# Minimal.net
KiCad netlist of a schematic drawn in EAGLE
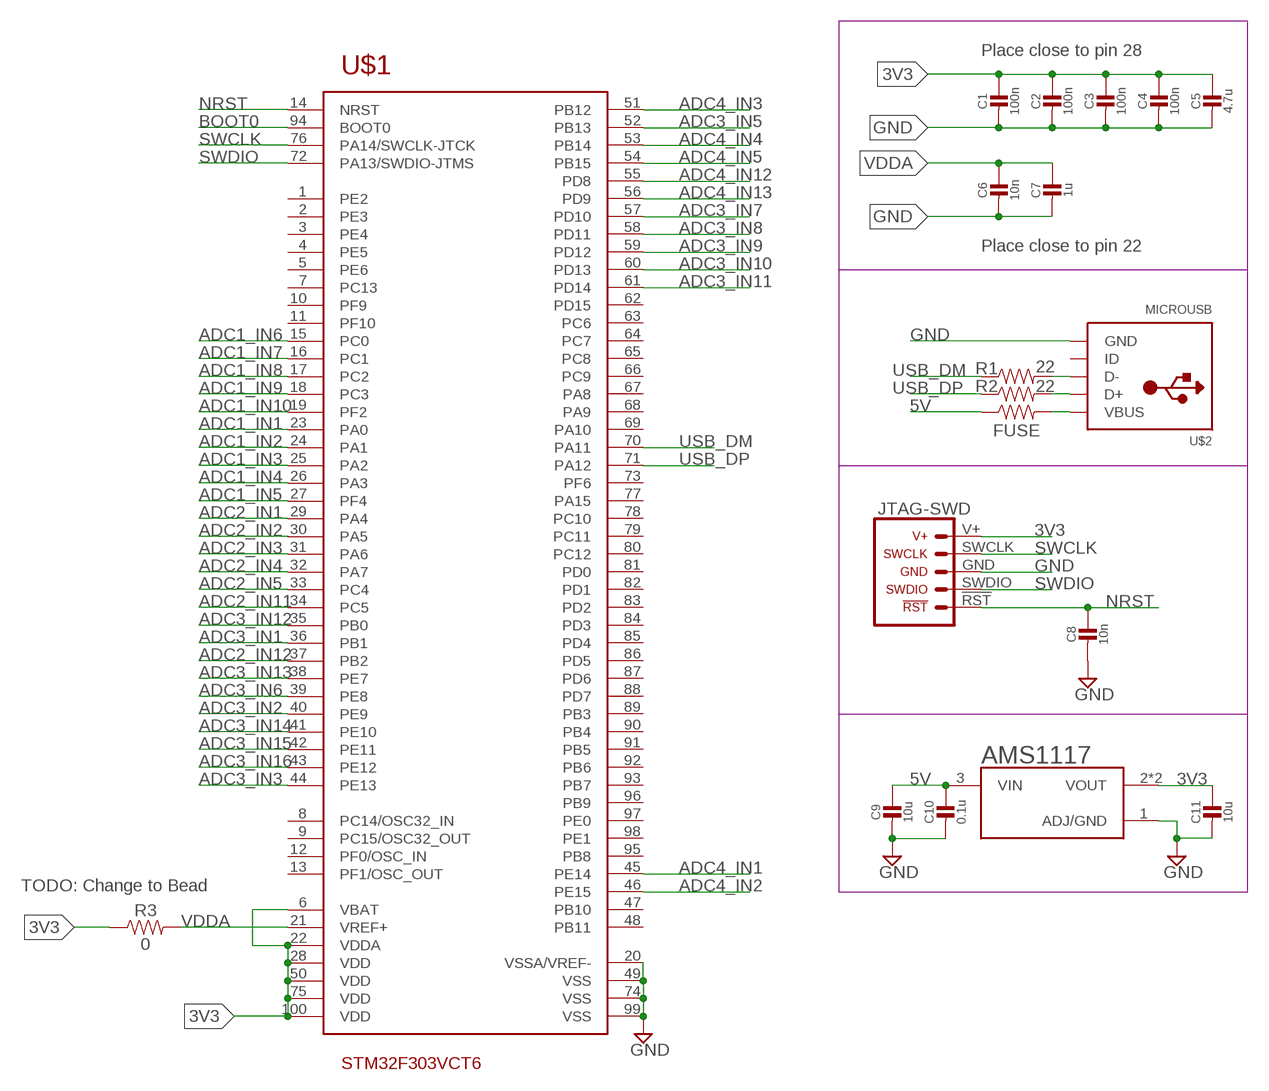
[diagram p0: schematic, sheet 1]
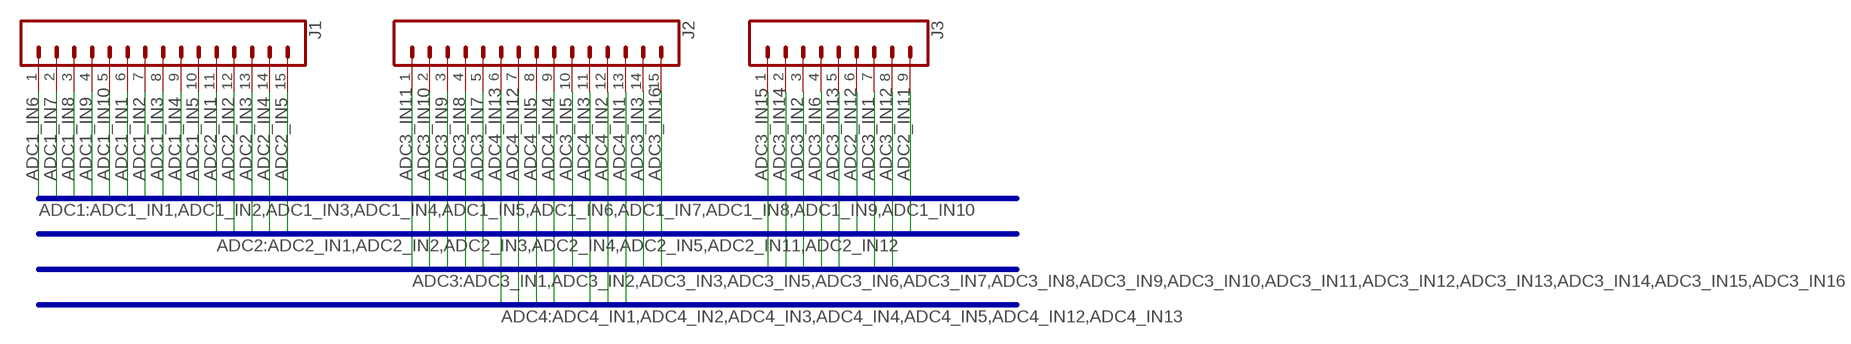
[diagram p1: schematic, sheet 2]

(export (version "E")
  (design (tool "Eeschema 10.0.6"))
  (components
    (comp (ref "J1")
      (value "CONN_15")
      (footprint "eagle-import:1X15")
      (libsource (lib "eagle-import") (part "CONN_15"))
    )
    (comp (ref "J2")
      (value "CONN_15")
      (footprint "eagle-import:1X15")
      (libsource (lib "eagle-import") (part "CONN_15"))
    )
    (comp (ref "J3")
      (value "CONN_09")
      (footprint "eagle-import:1X09")
      (libsource (lib "eagle-import") (part "CONN_09"))
    )
    (comp (ref "AMS1117")
      (value "3.3V")
      (footprint "eagle-import:SOT89")
      (libsource (lib "eagle-import") (part "VREG_AMS1117SMALL"))
    )
    (comp (ref "C1")
      (value "100n")
      (footprint "eagle-import:CAP_0603")
      (libsource (lib "eagle-import") (part "CAP_CERAMIC_0603"))
    )
    (comp (ref "C2")
      (value "100n")
      (footprint "eagle-import:CAP_0603")
      (libsource (lib "eagle-import") (part "CAP_CERAMIC_0603"))
    )
    (comp (ref "C3")
      (value "100n")
      (footprint "eagle-import:CAP_0603")
      (libsource (lib "eagle-import") (part "CAP_CERAMIC_0603"))
    )
    (comp (ref "C4")
      (value "100n")
      (footprint "eagle-import:CAP_0603")
      (libsource (lib "eagle-import") (part "CAP_CERAMIC_0603"))
    )
    (comp (ref "C5")
      (value "4.7u")
      (footprint "eagle-import:CAP_0603")
      (libsource (lib "eagle-import") (part "CAP_CERAMIC_0603"))
    )
    (comp (ref "C6")
      (value "10n")
      (footprint "eagle-import:CAP_0603")
      (libsource (lib "eagle-import") (part "CAP_CERAMIC_0603"))
    )
    (comp (ref "C7")
      (value "1u")
      (footprint "eagle-import:CAP_0603")
      (libsource (lib "eagle-import") (part "CAP_CERAMIC_0603"))
    )
    (comp (ref "C8")
      (value "10n")
      (footprint "eagle-import:CAP_0603")
      (libsource (lib "eagle-import") (part "CAP_CERAMIC_0603"))
    )
    (comp (ref "C9")
      (value "10u")
      (footprint "eagle-import:CAP_0603")
      (libsource (lib "eagle-import") (part "CAP_CERAMIC_0603"))
    )
    (comp (ref "C10")
      (value "0.1u")
      (footprint "eagle-import:CAP_0603")
      (libsource (lib "eagle-import") (part "CAP_CERAMIC_0603"))
    )
    (comp (ref "C11")
      (value "10u")
      (footprint "eagle-import:CAP_0603")
      (libsource (lib "eagle-import") (part "CAP_CERAMIC_0603"))
    )
    (comp (ref "FUSE")
      (value "RESISTOR1206")
      (footprint "eagle-import:1206")
      (libsource (lib "eagle-import") (part "RESISTOR1206"))
    )
    (comp (ref "R1")
      (value "22")
      (footprint "eagle-import:0603")
      (libsource (lib "eagle-import") (part "RESISTOR0603"))
    )
    (comp (ref "R2")
      (value "22")
      (footprint "eagle-import:0603")
      (libsource (lib "eagle-import") (part "RESISTOR0603"))
    )
    (comp (ref "R3")
      (value "0")
      (footprint "eagle-import:0603")
      (libsource (lib "eagle-import") (part "RESISTOR0603"))
    )
    (comp (ref "U$1")
      (value "STM32F303VCT6")
      (footprint "eagle-import:LQFP-100")
      (libsource (lib "eagle-import") (part "STM32F303VCT6"))
    )
    (comp (ref "U$2")
      (value "MICROUSB")
      (footprint "eagle-import:MICROUSB")
      (libsource (lib "eagle-import") (part "MICROUSB"))
    )
    (comp (ref "U$3")
      (value "JTAG-SWD")
      (footprint "eagle-import:JTAG_SWD")
      (libsource (lib "eagle-import") (part "JTAG-SWD"))
    )
  )
  (nets
    (net (code "9") (name "3V3") (class "Default")
      (node (ref "AMS1117") (pin "2") (pinfunction "VOUT_2") (pintype "output"))
      (node (ref "AMS1117") (pin "2@1") (pinfunction "VOUT_2@1") (pintype "output"))
      (node (ref "C1") (pin "1") (pinfunction "1_1") (pintype "passive"))
      (node (ref "C11") (pin "1") (pinfunction "1_1") (pintype "passive"))
      (node (ref "C2") (pin "1") (pinfunction "1_1") (pintype "passive"))
      (node (ref "C3") (pin "1") (pinfunction "1_1") (pintype "passive"))
      (node (ref "C4") (pin "1") (pinfunction "1_1") (pintype "passive"))
      (node (ref "C5") (pin "1") (pinfunction "1_1") (pintype "passive"))
      (node (ref "R3") (pin "1") (pinfunction "1_1") (pintype "passive"))
      (node (ref "U$1") (pin "100") (pinfunction "VDD_100") (pintype "bidirectional"))
      (node (ref "U$1") (pin "22") (pinfunction "VDDA_22") (pintype "bidirectional"))
      (node (ref "U$1") (pin "28") (pinfunction "VDD_28") (pintype "bidirectional"))
      (node (ref "U$1") (pin "50") (pinfunction "VDD_50") (pintype "bidirectional"))
      (node (ref "U$1") (pin "6") (pinfunction "VBAT_6") (pintype "bidirectional"))
      (node (ref "U$1") (pin "75") (pinfunction "VDD_75") (pintype "bidirectional"))
      (node (ref "U$3") (pin "V+") (pinfunction "V+_V+") (pintype "passive"))
    )
    (net (code "10") (name "5V") (class "Default")
      (node (ref "AMS1117") (pin "3") (pinfunction "VIN_3") (pintype "input"))
      (node (ref "C10") (pin "1") (pinfunction "1_1") (pintype "passive"))
      (node (ref "C9") (pin "1") (pinfunction "1_1") (pintype "passive"))
      (node (ref "FUSE") (pin "1") (pinfunction "1_1") (pintype "passive"))
    )
    (net (code "11") (name "ADC1_IN1") (class "Default")
      (node (ref "J1") (pin "6") (pinfunction "6_6") (pintype "passive"))
      (node (ref "U$1") (pin "23") (pinfunction "PA0_23") (pintype "bidirectional"))
    )
    (net (code "12") (name "ADC1_IN2") (class "Default")
      (node (ref "J1") (pin "7") (pinfunction "7_7") (pintype "passive"))
      (node (ref "U$1") (pin "24") (pinfunction "PA1_24") (pintype "bidirectional"))
    )
    (net (code "13") (name "ADC1_IN3") (class "Default")
      (node (ref "J1") (pin "8") (pinfunction "8_8") (pintype "passive"))
      (node (ref "U$1") (pin "25") (pinfunction "PA2_25") (pintype "bidirectional"))
    )
    (net (code "14") (name "ADC1_IN4") (class "Default")
      (node (ref "J1") (pin "9") (pinfunction "9_9") (pintype "passive"))
      (node (ref "U$1") (pin "26") (pinfunction "PA3_26") (pintype "bidirectional"))
    )
    (net (code "15") (name "ADC1_IN5") (class "Default")
      (node (ref "J1") (pin "10") (pinfunction "10_10") (pintype "passive"))
      (node (ref "U$1") (pin "27") (pinfunction "PF4_27") (pintype "bidirectional"))
    )
    (net (code "16") (name "ADC1_IN6") (class "Default")
      (node (ref "J1") (pin "1") (pinfunction "1_1") (pintype "passive"))
      (node (ref "U$1") (pin "15") (pinfunction "PC0_15") (pintype "bidirectional"))
    )
    (net (code "17") (name "ADC1_IN7") (class "Default")
      (node (ref "J1") (pin "2") (pinfunction "2_2") (pintype "passive"))
      (node (ref "U$1") (pin "16") (pinfunction "PC1_16") (pintype "bidirectional"))
    )
    (net (code "18") (name "ADC1_IN8") (class "Default")
      (node (ref "J1") (pin "3") (pinfunction "3_3") (pintype "passive"))
      (node (ref "U$1") (pin "17") (pinfunction "PC2_17") (pintype "bidirectional"))
    )
    (net (code "19") (name "ADC1_IN9") (class "Default")
      (node (ref "J1") (pin "4") (pinfunction "4_4") (pintype "passive"))
      (node (ref "U$1") (pin "18") (pinfunction "PC3_18") (pintype "bidirectional"))
    )
    (net (code "20") (name "ADC1_IN10") (class "Default")
      (node (ref "J1") (pin "5") (pinfunction "5_5") (pintype "passive"))
      (node (ref "U$1") (pin "19") (pinfunction "PF2_19") (pintype "bidirectional"))
    )
    (net (code "21") (name "ADC2_IN1") (class "Default")
      (node (ref "J1") (pin "11") (pinfunction "11_11") (pintype "passive"))
      (node (ref "U$1") (pin "29") (pinfunction "PA4_29") (pintype "bidirectional"))
    )
    (net (code "22") (name "ADC2_IN2") (class "Default")
      (node (ref "J1") (pin "12") (pinfunction "12_12") (pintype "passive"))
      (node (ref "U$1") (pin "30") (pinfunction "PA5_30") (pintype "bidirectional"))
    )
    (net (code "23") (name "ADC2_IN3") (class "Default")
      (node (ref "J1") (pin "13") (pinfunction "13_13") (pintype "passive"))
      (node (ref "U$1") (pin "31") (pinfunction "PA6_31") (pintype "bidirectional"))
    )
    (net (code "24") (name "ADC2_IN4") (class "Default")
      (node (ref "J1") (pin "14") (pinfunction "14_14") (pintype "passive"))
      (node (ref "U$1") (pin "32") (pinfunction "PA7_32") (pintype "bidirectional"))
    )
    (net (code "25") (name "ADC2_IN5") (class "Default")
      (node (ref "J1") (pin "15") (pinfunction "15_15") (pintype "passive"))
      (node (ref "U$1") (pin "33") (pinfunction "PC4_33") (pintype "bidirectional"))
    )
    (net (code "26") (name "ADC2_IN11") (class "Default")
      (node (ref "J3") (pin "9") (pinfunction "9_9") (pintype "passive"))
      (node (ref "U$1") (pin "34") (pinfunction "PC5_34") (pintype "bidirectional"))
    )
    (net (code "27") (name "ADC2_IN12") (class "Default")
      (node (ref "J3") (pin "6") (pinfunction "6_6") (pintype "passive"))
      (node (ref "U$1") (pin "37") (pinfunction "PB2_37") (pintype "bidirectional"))
    )
    (net (code "28") (name "ADC3_IN1") (class "Default")
      (node (ref "J3") (pin "7") (pinfunction "7_7") (pintype "passive"))
      (node (ref "U$1") (pin "36") (pinfunction "PB1_36") (pintype "bidirectional"))
    )
    (net (code "29") (name "ADC3_IN2") (class "Default")
      (node (ref "J3") (pin "3") (pinfunction "3_3") (pintype "passive"))
      (node (ref "U$1") (pin "40") (pinfunction "PE9_40") (pintype "bidirectional"))
    )
    (net (code "30") (name "ADC3_IN3") (class "Default")
      (node (ref "J2") (pin "14") (pinfunction "14_14") (pintype "passive"))
      (node (ref "U$1") (pin "44") (pinfunction "PE13_44") (pintype "bidirectional"))
    )
    (net (code "31") (name "ADC3_IN5") (class "Default")
      (node (ref "J2") (pin "10") (pinfunction "10_10") (pintype "passive"))
      (node (ref "U$1") (pin "52") (pinfunction "PB13_52") (pintype "bidirectional"))
    )
    (net (code "32") (name "ADC3_IN6") (class "Default")
      (node (ref "J3") (pin "4") (pinfunction "4_4") (pintype "passive"))
      (node (ref "U$1") (pin "39") (pinfunction "PE8_39") (pintype "bidirectional"))
    )
    (net (code "33") (name "ADC3_IN7") (class "Default")
      (node (ref "J2") (pin "5") (pinfunction "5_5") (pintype "passive"))
      (node (ref "U$1") (pin "57") (pinfunction "PD10_57") (pintype "bidirectional"))
    )
    (net (code "34") (name "ADC3_IN8") (class "Default")
      (node (ref "J2") (pin "4") (pinfunction "4_4") (pintype "passive"))
      (node (ref "U$1") (pin "58") (pinfunction "PD11_58") (pintype "bidirectional"))
    )
    (net (code "35") (name "ADC3_IN9") (class "Default")
      (node (ref "J2") (pin "3") (pinfunction "3_3") (pintype "passive"))
      (node (ref "U$1") (pin "59") (pinfunction "PD12_59") (pintype "bidirectional"))
    )
    (net (code "36") (name "ADC3_IN10") (class "Default")
      (node (ref "J2") (pin "2") (pinfunction "2_2") (pintype "passive"))
      (node (ref "U$1") (pin "60") (pinfunction "PD13_60") (pintype "bidirectional"))
    )
    (net (code "37") (name "ADC3_IN11") (class "Default")
      (node (ref "J2") (pin "1") (pinfunction "1_1") (pintype "passive"))
      (node (ref "U$1") (pin "61") (pinfunction "PD14_61") (pintype "bidirectional"))
    )
    (net (code "38") (name "ADC3_IN12") (class "Default")
      (node (ref "J3") (pin "8") (pinfunction "8_8") (pintype "passive"))
      (node (ref "U$1") (pin "35") (pinfunction "PB0_35") (pintype "bidirectional"))
    )
    (net (code "39") (name "ADC3_IN13") (class "Default")
      (node (ref "J3") (pin "5") (pinfunction "5_5") (pintype "passive"))
      (node (ref "U$1") (pin "38") (pinfunction "PE7_38") (pintype "bidirectional"))
    )
    (net (code "40") (name "ADC3_IN14") (class "Default")
      (node (ref "J3") (pin "2") (pinfunction "2_2") (pintype "passive"))
      (node (ref "U$1") (pin "41") (pinfunction "PE10_41") (pintype "bidirectional"))
    )
    (net (code "41") (name "ADC3_IN15") (class "Default")
      (node (ref "J3") (pin "1") (pinfunction "1_1") (pintype "passive"))
      (node (ref "U$1") (pin "42") (pinfunction "PE11_42") (pintype "bidirectional"))
    )
    (net (code "42") (name "ADC3_IN16") (class "Default")
      (node (ref "J2") (pin "15") (pinfunction "15_15") (pintype "passive"))
      (node (ref "U$1") (pin "43") (pinfunction "PE12_43") (pintype "bidirectional"))
    )
    (net (code "43") (name "ADC4_IN1") (class "Default")
      (node (ref "J2") (pin "13") (pinfunction "13_13") (pintype "passive"))
      (node (ref "U$1") (pin "45") (pinfunction "PE14_45") (pintype "bidirectional"))
    )
    (net (code "44") (name "ADC4_IN2") (class "Default")
      (node (ref "J2") (pin "12") (pinfunction "12_12") (pintype "passive"))
      (node (ref "U$1") (pin "46") (pinfunction "PE15_46") (pintype "bidirectional"))
    )
    (net (code "45") (name "ADC4_IN3") (class "Default")
      (node (ref "J2") (pin "11") (pinfunction "11_11") (pintype "passive"))
      (node (ref "U$1") (pin "51") (pinfunction "PB12_51") (pintype "bidirectional"))
    )
    (net (code "46") (name "ADC4_IN4") (class "Default")
      (node (ref "J2") (pin "9") (pinfunction "9_9") (pintype "passive"))
      (node (ref "U$1") (pin "53") (pinfunction "PB14_53") (pintype "bidirectional"))
    )
    (net (code "47") (name "ADC4_IN5") (class "Default")
      (node (ref "J2") (pin "8") (pinfunction "8_8") (pintype "passive"))
      (node (ref "U$1") (pin "54") (pinfunction "PB15_54") (pintype "bidirectional"))
    )
    (net (code "48") (name "ADC4_IN12") (class "Default")
      (node (ref "J2") (pin "7") (pinfunction "7_7") (pintype "passive"))
      (node (ref "U$1") (pin "55") (pinfunction "PD8_55") (pintype "bidirectional"))
    )
    (net (code "49") (name "ADC4_IN13") (class "Default")
      (node (ref "J2") (pin "6") (pinfunction "6_6") (pintype "passive"))
      (node (ref "U$1") (pin "56") (pinfunction "PD9_56") (pintype "bidirectional"))
    )
    (net (code "50") (name "BOOT0") (class "Default")
      (node (ref "U$1") (pin "94") (pinfunction "BOOT0_94") (pintype "bidirectional"))
    )
    (net (code "51") (name "GND") (class "Default")
      (node (ref "AMS1117") (pin "1") (pinfunction "ADJ/GND_1") (pintype "power_in"))
      (node (ref "C1") (pin "2") (pinfunction "2_2") (pintype "passive"))
      (node (ref "C10") (pin "2") (pinfunction "2_2") (pintype "passive"))
      (node (ref "C11") (pin "2") (pinfunction "2_2") (pintype "passive"))
      (node (ref "C2") (pin "2") (pinfunction "2_2") (pintype "passive"))
      (node (ref "C3") (pin "2") (pinfunction "2_2") (pintype "passive"))
      (node (ref "C4") (pin "2") (pinfunction "2_2") (pintype "passive"))
      (node (ref "C5") (pin "2") (pinfunction "2_2") (pintype "passive"))
      (node (ref "C6") (pin "2") (pinfunction "2_2") (pintype "passive"))
      (node (ref "C7") (pin "2") (pinfunction "2_2") (pintype "passive"))
      (node (ref "C8") (pin "2") (pinfunction "2_2") (pintype "passive"))
      (node (ref "C9") (pin "2") (pinfunction "2_2") (pintype "passive"))
      (node (ref "U$1") (pin "20") (pinfunction "VSSA/VREF-_20") (pintype "bidirectional"))
      (node (ref "U$1") (pin "49") (pinfunction "VSS_49") (pintype "bidirectional"))
      (node (ref "U$1") (pin "74") (pinfunction "VSS_74") (pintype "bidirectional"))
      (node (ref "U$1") (pin "99") (pinfunction "VSS_99") (pintype "bidirectional"))
      (node (ref "U$2") (pin "GND") (pinfunction "GND_GND") (pintype "power_in"))
      (node (ref "U$2") (pin "S1") (pinfunction "GND_S1") (pintype "power_in"))
      (node (ref "U$2") (pin "S2") (pinfunction "GND_S2") (pintype "power_in"))
      (node (ref "U$2") (pin "S3") (pinfunction "GND_S3") (pintype "power_in"))
      (node (ref "U$2") (pin "S4") (pinfunction "GND_S4") (pintype "power_in"))
      (node (ref "U$2") (pin "S5") (pinfunction "GND_S5") (pintype "power_in"))
      (node (ref "U$2") (pin "S6") (pinfunction "GND_S6") (pintype "power_in"))
      (node (ref "U$3") (pin "GND") (pinfunction "GND_GND") (pintype "passive"))
    )
    (net (code "52") (name "NRST") (class "Default")
      (node (ref "C8") (pin "1") (pinfunction "1_1") (pintype "passive"))
      (node (ref "U$1") (pin "14") (pinfunction "NRST_14") (pintype "bidirectional"))
      (node (ref "U$3") (pin "!RST") (pinfunction "~{RST}_!RST") (pintype "passive"))
    )
    (net (code "53") (name "Net-(FUSE-Pad2)") (class "Default")
      (node (ref "FUSE") (pin "2") (pinfunction "2_2") (pintype "passive"))
      (node (ref "U$2") (pin "VBUS") (pinfunction "VBUS_VBUS") (pintype "power_in"))
    )
    (net (code "54") (name "Net-(R1-Pad2)") (class "Default")
      (node (ref "R1") (pin "2") (pinfunction "2_2") (pintype "passive"))
      (node (ref "U$2") (pin "D-") (pinfunction "D-_D-") (pintype "bidirectional"))
    )
    (net (code "55") (name "Net-(R2-Pad2)") (class "Default")
      (node (ref "R2") (pin "2") (pinfunction "2_2") (pintype "passive"))
      (node (ref "U$2") (pin "D+") (pinfunction "D+_D+") (pintype "bidirectional"))
    )
    (net (code "56") (name "SWCLK") (class "Default")
      (node (ref "U$1") (pin "76") (pinfunction "PA14/SWCLK-JTCK_76") (pintype "bidirectional"))
      (node (ref "U$3") (pin "SWCLK") (pinfunction "SWCLK_SWCLK") (pintype "passive"))
    )
    (net (code "57") (name "SWDIO") (class "Default")
      (node (ref "U$1") (pin "72") (pinfunction "PA13/SWDIO-JTMS_72") (pintype "bidirectional"))
      (node (ref "U$3") (pin "SWDIO") (pinfunction "SWDIO_SWDIO") (pintype "passive"))
    )
    (net (code "58") (name "USB_DM") (class "Default")
      (node (ref "R1") (pin "1") (pinfunction "1_1") (pintype "passive"))
      (node (ref "U$1") (pin "70") (pinfunction "PA11_70") (pintype "bidirectional"))
    )
    (net (code "59") (name "USB_DP") (class "Default")
      (node (ref "R2") (pin "1") (pinfunction "1_1") (pintype "passive"))
      (node (ref "U$1") (pin "71") (pinfunction "PA12_71") (pintype "bidirectional"))
    )
    (net (code "60") (name "VDDA") (class "Default")
      (node (ref "C6") (pin "1") (pinfunction "1_1") (pintype "passive"))
      (node (ref "C7") (pin "1") (pinfunction "1_1") (pintype "passive"))
      (node (ref "R3") (pin "2") (pinfunction "2_2") (pintype "passive"))
      (node (ref "U$1") (pin "21") (pinfunction "VREF+_21") (pintype "bidirectional"))
    )
    (net (code "61") (name "unconnected-(U$1-PA8-Pad67)") (class "Default")
      (node (ref "U$1") (pin "67") (pinfunction "PA8_67") (pintype "bidirectional"))
    )
    (net (code "62") (name "unconnected-(U$1-PA9-Pad68)") (class "Default")
      (node (ref "U$1") (pin "68") (pinfunction "PA9_68") (pintype "bidirectional"))
    )
    (net (code "63") (name "unconnected-(U$1-PA10-Pad69)") (class "Default")
      (node (ref "U$1") (pin "69") (pinfunction "PA10_69") (pintype "bidirectional"))
    )
    (net (code "64") (name "unconnected-(U$1-PA15-Pad77)") (class "Default")
      (node (ref "U$1") (pin "77") (pinfunction "PA15_77") (pintype "bidirectional"))
    )
    (net (code "65") (name "unconnected-(U$1-PB3-Pad89)") (class "Default")
      (node (ref "U$1") (pin "89") (pinfunction "PB3_89") (pintype "bidirectional"))
    )
    (net (code "66") (name "unconnected-(U$1-PB4-Pad90)") (class "Default")
      (node (ref "U$1") (pin "90") (pinfunction "PB4_90") (pintype "bidirectional"))
    )
    (net (code "67") (name "unconnected-(U$1-PB5-Pad91)") (class "Default")
      (node (ref "U$1") (pin "91") (pinfunction "PB5_91") (pintype "bidirectional"))
    )
    (net (code "68") (name "unconnected-(U$1-PB6-Pad92)") (class "Default")
      (node (ref "U$1") (pin "92") (pinfunction "PB6_92") (pintype "bidirectional"))
    )
    (net (code "69") (name "unconnected-(U$1-PB7-Pad93)") (class "Default")
      (node (ref "U$1") (pin "93") (pinfunction "PB7_93") (pintype "bidirectional"))
    )
    (net (code "70") (name "unconnected-(U$1-PB8-Pad95)") (class "Default")
      (node (ref "U$1") (pin "95") (pinfunction "PB8_95") (pintype "bidirectional"))
    )
    (net (code "71") (name "unconnected-(U$1-PB9-Pad96)") (class "Default")
      (node (ref "U$1") (pin "96") (pinfunction "PB9_96") (pintype "bidirectional"))
    )
    (net (code "72") (name "unconnected-(U$1-PB10-Pad47)") (class "Default")
      (node (ref "U$1") (pin "47") (pinfunction "PB10_47") (pintype "bidirectional"))
    )
    (net (code "73") (name "unconnected-(U$1-PB11-Pad48)") (class "Default")
      (node (ref "U$1") (pin "48") (pinfunction "PB11_48") (pintype "bidirectional"))
    )
    (net (code "74") (name "unconnected-(U$1-PC6-Pad63)") (class "Default")
      (node (ref "U$1") (pin "63") (pinfunction "PC6_63") (pintype "bidirectional"))
    )
    (net (code "75") (name "unconnected-(U$1-PC7-Pad64)") (class "Default")
      (node (ref "U$1") (pin "64") (pinfunction "PC7_64") (pintype "bidirectional"))
    )
    (net (code "76") (name "unconnected-(U$1-PC8-Pad65)") (class "Default")
      (node (ref "U$1") (pin "65") (pinfunction "PC8_65") (pintype "bidirectional"))
    )
    (net (code "77") (name "unconnected-(U$1-PC9-Pad66)") (class "Default")
      (node (ref "U$1") (pin "66") (pinfunction "PC9_66") (pintype "bidirectional"))
    )
    (net (code "78") (name "unconnected-(U$1-PC10-Pad78)") (class "Default")
      (node (ref "U$1") (pin "78") (pinfunction "PC10_78") (pintype "bidirectional"))
    )
    (net (code "79") (name "unconnected-(U$1-PC11-Pad79)") (class "Default")
      (node (ref "U$1") (pin "79") (pinfunction "PC11_79") (pintype "bidirectional"))
    )
    (net (code "80") (name "unconnected-(U$1-PC12-Pad80)") (class "Default")
      (node (ref "U$1") (pin "80") (pinfunction "PC12_80") (pintype "bidirectional"))
    )
    (net (code "81") (name "unconnected-(U$1-PC13-Pad7)") (class "Default")
      (node (ref "U$1") (pin "7") (pinfunction "PC13_7") (pintype "bidirectional"))
    )
    (net (code "82") (name "unconnected-(U$1-PC14{slash}OSC32_IN-Pad8)") (class "Default")
      (node (ref "U$1") (pin "8") (pinfunction "PC14/OSC32_IN_8") (pintype "bidirectional"))
    )
    (net (code "83") (name "unconnected-(U$1-PC15{slash}OSC32_OUT-Pad9)") (class "Default")
      (node (ref "U$1") (pin "9") (pinfunction "PC15/OSC32_OUT_9") (pintype "bidirectional"))
    )
    (net (code "84") (name "unconnected-(U$1-PD0-Pad81)") (class "Default")
      (node (ref "U$1") (pin "81") (pinfunction "PD0_81") (pintype "bidirectional"))
    )
    (net (code "85") (name "unconnected-(U$1-PD1-Pad82)") (class "Default")
      (node (ref "U$1") (pin "82") (pinfunction "PD1_82") (pintype "bidirectional"))
    )
    (net (code "86") (name "unconnected-(U$1-PD2-Pad83)") (class "Default")
      (node (ref "U$1") (pin "83") (pinfunction "PD2_83") (pintype "bidirectional"))
    )
    (net (code "87") (name "unconnected-(U$1-PD3-Pad84)") (class "Default")
      (node (ref "U$1") (pin "84") (pinfunction "PD3_84") (pintype "bidirectional"))
    )
    (net (code "88") (name "unconnected-(U$1-PD4-Pad85)") (class "Default")
      (node (ref "U$1") (pin "85") (pinfunction "PD4_85") (pintype "bidirectional"))
    )
    (net (code "89") (name "unconnected-(U$1-PD5-Pad86)") (class "Default")
      (node (ref "U$1") (pin "86") (pinfunction "PD5_86") (pintype "bidirectional"))
    )
    (net (code "90") (name "unconnected-(U$1-PD6-Pad87)") (class "Default")
      (node (ref "U$1") (pin "87") (pinfunction "PD6_87") (pintype "bidirectional"))
    )
    (net (code "91") (name "unconnected-(U$1-PD7-Pad88)") (class "Default")
      (node (ref "U$1") (pin "88") (pinfunction "PD7_88") (pintype "bidirectional"))
    )
    (net (code "92") (name "unconnected-(U$1-PD15-Pad62)") (class "Default")
      (node (ref "U$1") (pin "62") (pinfunction "PD15_62") (pintype "bidirectional"))
    )
    (net (code "93") (name "unconnected-(U$1-PE0-Pad97)") (class "Default")
      (node (ref "U$1") (pin "97") (pinfunction "PE0_97") (pintype "bidirectional"))
    )
    (net (code "94") (name "unconnected-(U$1-PE1-Pad98)") (class "Default")
      (node (ref "U$1") (pin "98") (pinfunction "PE1_98") (pintype "bidirectional"))
    )
    (net (code "95") (name "unconnected-(U$1-PE2-Pad1)") (class "Default")
      (node (ref "U$1") (pin "1") (pinfunction "PE2_1") (pintype "bidirectional"))
    )
    (net (code "96") (name "unconnected-(U$1-PE3-Pad2)") (class "Default")
      (node (ref "U$1") (pin "2") (pinfunction "PE3_2") (pintype "bidirectional"))
    )
    (net (code "97") (name "unconnected-(U$1-PE4-Pad3)") (class "Default")
      (node (ref "U$1") (pin "3") (pinfunction "PE4_3") (pintype "bidirectional"))
    )
    (net (code "98") (name "unconnected-(U$1-PE5-Pad4)") (class "Default")
      (node (ref "U$1") (pin "4") (pinfunction "PE5_4") (pintype "bidirectional"))
    )
    (net (code "99") (name "unconnected-(U$1-PE6-Pad5)") (class "Default")
      (node (ref "U$1") (pin "5") (pinfunction "PE6_5") (pintype "bidirectional"))
    )
    (net (code "100") (name "unconnected-(U$1-PF0{slash}OSC_IN-Pad12)") (class "Default")
      (node (ref "U$1") (pin "12") (pinfunction "PF0/OSC_IN_12") (pintype "bidirectional"))
    )
    (net (code "101") (name "unconnected-(U$1-PF1{slash}OSC_OUT-Pad13)") (class "Default")
      (node (ref "U$1") (pin "13") (pinfunction "PF1/OSC_OUT_13") (pintype "bidirectional"))
    )
    (net (code "102") (name "unconnected-(U$1-PF6-Pad73)") (class "Default")
      (node (ref "U$1") (pin "73") (pinfunction "PF6_73") (pintype "bidirectional"))
    )
    (net (code "103") (name "unconnected-(U$1-PF9-Pad10)") (class "Default")
      (node (ref "U$1") (pin "10") (pinfunction "PF9_10") (pintype "bidirectional"))
    )
    (net (code "104") (name "unconnected-(U$1-PF10-Pad11)") (class "Default")
      (node (ref "U$1") (pin "11") (pinfunction "PF10_11") (pintype "bidirectional"))
    )
    (net (code "105") (name "unconnected-(U$2-PadID)") (class "Default")
      (node (ref "U$2") (pin "ID") (pinfunction "ID_ID") (pintype "bidirectional"))
    )
  )
)
